# garden.net
KiCad netlist of a schematic drawn in EAGLE
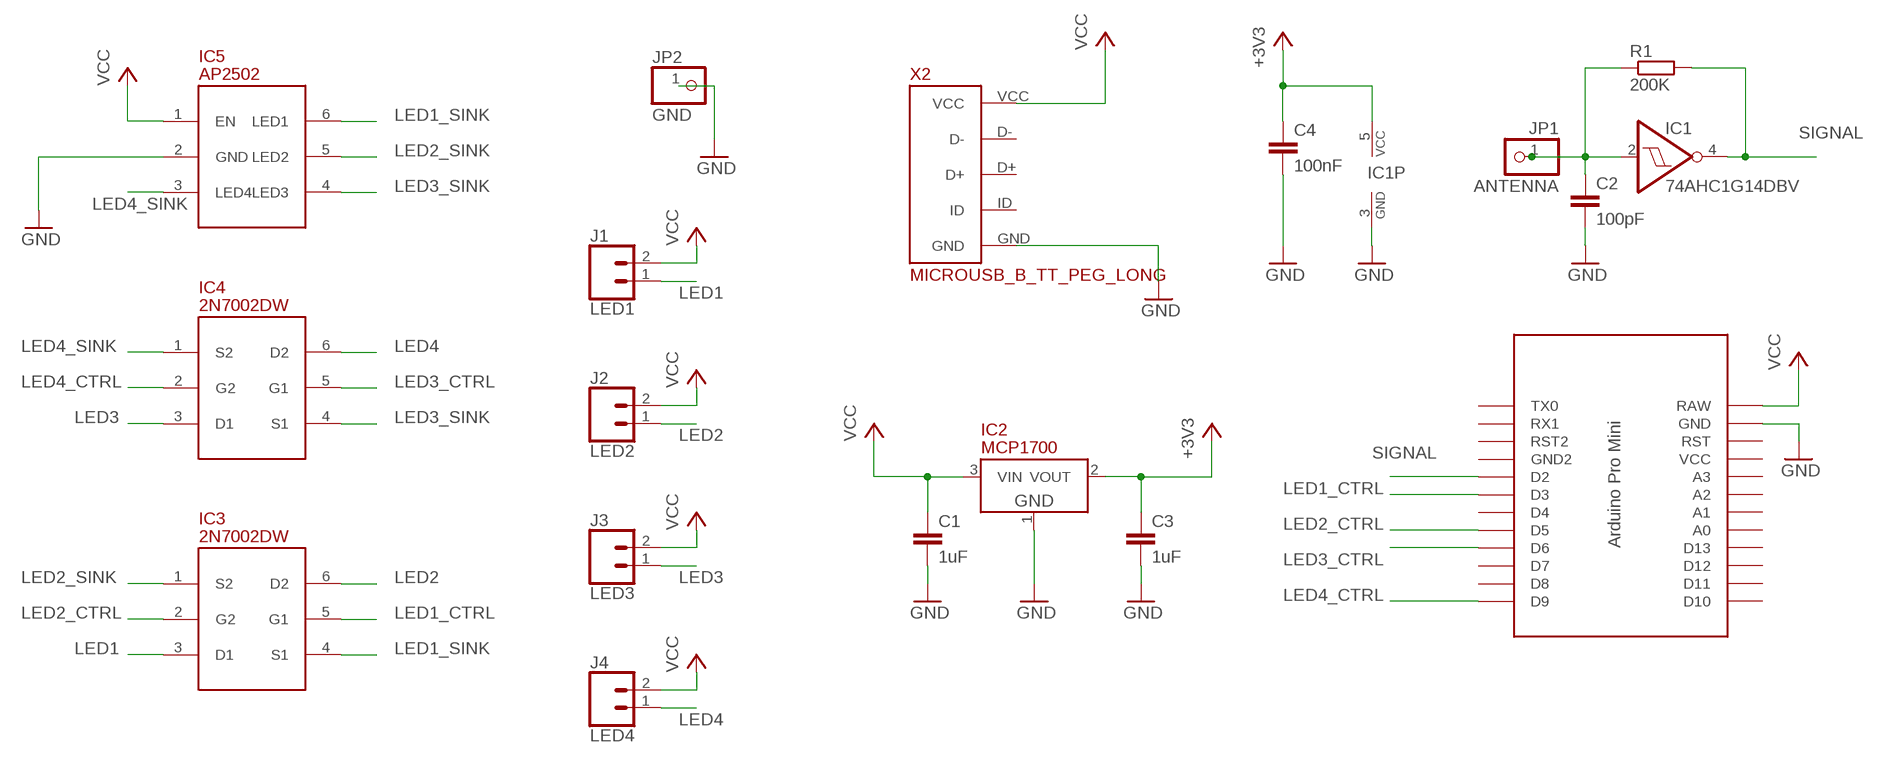
[diagram p0: schematic, sheet 1]

(export (version "E")
  (design (tool "Eeschema 10.0.6"))
  (components
    (comp (ref "C1")
      (value "1uF")
      (footprint "eagle-import:C0805")
      (libsource (lib "eagle-import") (part "C-EUC0805"))
    )
    (comp (ref "C2")
      (value "100pF")
      (footprint "eagle-import:C0805")
      (libsource (lib "eagle-import") (part "C-EUC0805"))
    )
    (comp (ref "C3")
      (value "1uF")
      (footprint "eagle-import:C0805")
      (libsource (lib "eagle-import") (part "C-EUC0805"))
    )
    (comp (ref "C4")
      (value "100nF")
      (footprint "eagle-import:C0805")
      (libsource (lib "eagle-import") (part "C-EUC0805"))
    )
    (comp (ref "IC1")
      (value "74AHC1G14DBV")
      (footprint "eagle-import:SOT23-5")
      (libsource (lib "eagle-import") (part "741G14DBVAHC"))
    )
    (comp (ref "IC2")
      (value "MCP1700")
      (footprint "eagle-import:SOT-23")
      (libsource (lib "eagle-import") (part "MCP1700"))
    )
    (comp (ref "IC3")
      (value "2N7002DW")
      (footprint "eagle-import:SOT363")
      (libsource (lib "eagle-import") (part "2N7002DW"))
    )
    (comp (ref "IC4")
      (value "2N7002DW")
      (footprint "eagle-import:SOT363")
      (libsource (lib "eagle-import") (part "2N7002DW"))
    )
    (comp (ref "IC5")
      (value "AP2502")
      (footprint "eagle-import:SOT-23-6")
      (libsource (lib "eagle-import") (part "AP2502"))
    )
    (comp (ref "J1")
      (value "LED1")
      (footprint "eagle-import:1X02")
      (libsource (lib "eagle-import") (part "CONN_02"))
    )
    (comp (ref "J2")
      (value "LED2")
      (footprint "eagle-import:1X02")
      (libsource (lib "eagle-import") (part "CONN_02"))
    )
    (comp (ref "J3")
      (value "LED3")
      (footprint "eagle-import:1X02")
      (libsource (lib "eagle-import") (part "CONN_02"))
    )
    (comp (ref "J4")
      (value "LED4")
      (footprint "eagle-import:1X02")
      (libsource (lib "eagle-import") (part "CONN_02"))
    )
    (comp (ref "JP1")
      (value "ANTENNA")
      (footprint "eagle-import:1X01")
      (libsource (lib "eagle-import") (part "PINHD-1X1"))
    )
    (comp (ref "JP2")
      (value "GND")
      (footprint "eagle-import:1X01")
      (libsource (lib "eagle-import") (part "PINHD-1X1"))
    )
    (comp (ref "R1")
      (value "200K")
      (footprint "eagle-import:R0805")
      (libsource (lib "eagle-import") (part "R-EU_R0805"))
    )
    (comp (ref "U$1")
      (value "PRO-MINI-TWO-SIDES-ONLY")
      (footprint "eagle-import:PRO-MINI-TWO-SIDES-ONLY")
      (libsource (lib "eagle-import") (part "PRO-MINI-TWO-SIDES-ONLY"))
    )
    (comp (ref "X2")
      (value "MICROUSB_B_TT_PEG_LONG")
      (footprint "eagle-import:MICROUSB_B_TT_PEG_LONG")
      (libsource (lib "eagle-import") (part "MICROUSB_B_TT_PEG_LONG"))
    )
  )
  (nets
    (net (code "1") (name "+3V3") (class "Default")
      (node (ref "C3") (pin "1") (pinfunction "1_1") (pintype "passive"))
      (node (ref "C4") (pin "1") (pinfunction "1_1") (pintype "passive"))
      (node (ref "IC1") (pin "5") (pinfunction "VCC_5") (pintype "power_in"))
      (node (ref "IC2") (pin "2") (pinfunction "VOUT_2") (pintype "output"))
    )
    (net (code "2") (name "/LED1") (class "Default")
      (node (ref "IC3") (pin "3") (pinfunction "D1_3") (pintype "input"))
      (node (ref "J1") (pin "1") (pinfunction "1_1") (pintype "passive"))
    )
    (net (code "3") (name "/LED1_CTRL") (class "Default")
      (node (ref "IC3") (pin "5") (pinfunction "G1_5") (pintype "input"))
      (node (ref "U$1") (pin "D3") (pinfunction "D3_D3") (pintype "bidirectional"))
    )
    (net (code "4") (name "/LED1_SINK") (class "Default")
      (node (ref "IC3") (pin "4") (pinfunction "S1_4") (pintype "output"))
      (node (ref "IC5") (pin "6") (pinfunction "LED1_6") (pintype "output"))
    )
    (net (code "5") (name "/LED2") (class "Default")
      (node (ref "IC3") (pin "6") (pinfunction "D2_6") (pintype "input"))
      (node (ref "J2") (pin "1") (pinfunction "1_1") (pintype "passive"))
    )
    (net (code "6") (name "/LED2_CTRL") (class "Default")
      (node (ref "IC3") (pin "2") (pinfunction "G2_2") (pintype "input"))
      (node (ref "U$1") (pin "D5") (pinfunction "D5_D5") (pintype "bidirectional"))
    )
    (net (code "7") (name "/LED2_SINK") (class "Default")
      (node (ref "IC3") (pin "1") (pinfunction "S2_1") (pintype "output"))
      (node (ref "IC5") (pin "5") (pinfunction "LED2_5") (pintype "output"))
    )
    (net (code "8") (name "/LED3") (class "Default")
      (node (ref "IC4") (pin "3") (pinfunction "D1_3") (pintype "input"))
      (node (ref "J3") (pin "1") (pinfunction "1_1") (pintype "passive"))
    )
    (net (code "9") (name "/LED3_CTRL") (class "Default")
      (node (ref "IC4") (pin "5") (pinfunction "G1_5") (pintype "input"))
      (node (ref "U$1") (pin "D6") (pinfunction "D6_D6") (pintype "bidirectional"))
    )
    (net (code "10") (name "/LED3_SINK") (class "Default")
      (node (ref "IC4") (pin "4") (pinfunction "S1_4") (pintype "output"))
      (node (ref "IC5") (pin "4") (pinfunction "LED3_4") (pintype "output"))
    )
    (net (code "11") (name "/LED4") (class "Default")
      (node (ref "IC4") (pin "6") (pinfunction "D2_6") (pintype "input"))
      (node (ref "J4") (pin "1") (pinfunction "1_1") (pintype "passive"))
    )
    (net (code "12") (name "/LED4_CTRL") (class "Default")
      (node (ref "IC4") (pin "2") (pinfunction "G2_2") (pintype "input"))
      (node (ref "U$1") (pin "D9") (pinfunction "D9_D9") (pintype "bidirectional"))
    )
    (net (code "13") (name "/LED4_SINK") (class "Default")
      (node (ref "IC4") (pin "1") (pinfunction "S2_1") (pintype "output"))
      (node (ref "IC5") (pin "3") (pinfunction "LED4_3") (pintype "output"))
    )
    (net (code "14") (name "/SIGNAL") (class "Default")
      (node (ref "IC1") (pin "4") (pinfunction "O_4") (pintype "output"))
      (node (ref "R1") (pin "2") (pinfunction "2_2") (pintype "passive"))
      (node (ref "U$1") (pin "D2") (pinfunction "D2_D2") (pintype "bidirectional"))
    )
    (net (code "15") (name "GND") (class "Default")
      (node (ref "C1") (pin "2") (pinfunction "2_2") (pintype "passive"))
      (node (ref "C2") (pin "2") (pinfunction "2_2") (pintype "passive"))
      (node (ref "C3") (pin "2") (pinfunction "2_2") (pintype "passive"))
      (node (ref "C4") (pin "2") (pinfunction "2_2") (pintype "passive"))
      (node (ref "IC1") (pin "3") (pinfunction "GND_3") (pintype "power_in"))
      (node (ref "IC2") (pin "1") (pinfunction "GND_1") (pintype "input"))
      (node (ref "IC5") (pin "2") (pinfunction "GND_2") (pintype "input"))
      (node (ref "JP2") (pin "1") (pinfunction "1_1") (pintype "passive"))
      (node (ref "U$1") (pin "GND") (pinfunction "GND_GND") (pintype "input"))
      (node (ref "X2") (pin "GND") (pinfunction "GND_GND") (pintype "power_in"))
    )
    (net (code "16") (name "Net-(IC1A-I)") (class "Default")
      (node (ref "C2") (pin "1") (pinfunction "1_1") (pintype "passive"))
      (node (ref "IC1") (pin "2") (pinfunction "I_2") (pintype "input"))
      (node (ref "JP1") (pin "1") (pinfunction "1_1") (pintype "passive"))
      (node (ref "R1") (pin "1") (pinfunction "1_1") (pintype "passive"))
    )
    (net (code "17") (name "VCC") (class "Default")
      (node (ref "C1") (pin "1") (pinfunction "1_1") (pintype "passive"))
      (node (ref "IC2") (pin "3") (pinfunction "VIN_3") (pintype "input"))
      (node (ref "IC5") (pin "1") (pinfunction "EN_1") (pintype "input"))
      (node (ref "J1") (pin "2") (pinfunction "2_2") (pintype "passive"))
      (node (ref "J2") (pin "2") (pinfunction "2_2") (pintype "passive"))
      (node (ref "J3") (pin "2") (pinfunction "2_2") (pintype "passive"))
      (node (ref "J4") (pin "2") (pinfunction "2_2") (pintype "passive"))
      (node (ref "U$1") (pin "RAW") (pinfunction "RAW_RAW") (pintype "power_in"))
      (node (ref "X2") (pin "VCC") (pinfunction "VCC_VCC") (pintype "power_in"))
    )
    (net (code "18") (name "unconnected-(U$1-GND2-PadGND1)") (class "Default")
      (node (ref "U$1") (pin "GND1") (pinfunction "GND2_GND1") (pintype "bidirectional"))
    )
    (net (code "19") (name "unconnected-(U$1-PadA0)") (class "Default")
      (node (ref "U$1") (pin "A0") (pinfunction "A0_A0") (pintype "bidirectional"))
    )
    (net (code "20") (name "unconnected-(U$1-PadA1)") (class "Default")
      (node (ref "U$1") (pin "A1") (pinfunction "A1_A1") (pintype "bidirectional"))
    )
    (net (code "21") (name "unconnected-(U$1-PadA2)") (class "Default")
      (node (ref "U$1") (pin "A2") (pinfunction "A2_A2") (pintype "bidirectional"))
    )
    (net (code "22") (name "unconnected-(U$1-PadA3)") (class "Default")
      (node (ref "U$1") (pin "A3") (pinfunction "A3_A3") (pintype "bidirectional"))
    )
    (net (code "23") (name "unconnected-(U$1-PadD4)") (class "Default")
      (node (ref "U$1") (pin "D4") (pinfunction "D4_D4") (pintype "bidirectional"))
    )
    (net (code "24") (name "unconnected-(U$1-PadD7)") (class "Default")
      (node (ref "U$1") (pin "D7") (pinfunction "D7_D7") (pintype "bidirectional"))
    )
    (net (code "25") (name "unconnected-(U$1-PadD8)") (class "Default")
      (node (ref "U$1") (pin "D8") (pinfunction "D8_D8") (pintype "bidirectional"))
    )
    (net (code "26") (name "unconnected-(U$1-PadD10)") (class "Default")
      (node (ref "U$1") (pin "D10") (pinfunction "D10_D10") (pintype "bidirectional"))
    )
    (net (code "27") (name "unconnected-(U$1-PadD11)") (class "Default")
      (node (ref "U$1") (pin "D11") (pinfunction "D11_D11") (pintype "bidirectional"))
    )
    (net (code "28") (name "unconnected-(U$1-PadD12)") (class "Default")
      (node (ref "U$1") (pin "D12") (pinfunction "D12_D12") (pintype "bidirectional"))
    )
    (net (code "29") (name "unconnected-(U$1-PadD13)") (class "Default")
      (node (ref "U$1") (pin "D13") (pinfunction "D13_D13") (pintype "bidirectional"))
    )
    (net (code "30") (name "unconnected-(U$1-PadRST)") (class "Default")
      (node (ref "U$1") (pin "RST") (pinfunction "RST_RST") (pintype "bidirectional"))
    )
    (net (code "31") (name "unconnected-(U$1-PadRX1)") (class "Default")
      (node (ref "U$1") (pin "RX1") (pinfunction "RX1_RX1") (pintype "bidirectional"))
    )
    (net (code "32") (name "unconnected-(U$1-PadTX0)") (class "Default")
      (node (ref "U$1") (pin "TX0") (pinfunction "TX0_TX0") (pintype "bidirectional"))
    )
    (net (code "33") (name "unconnected-(U$1-PadVCC)") (class "Default")
      (node (ref "U$1") (pin "VCC") (pinfunction "VCC_VCC") (pintype "bidirectional"))
    )
    (net (code "34") (name "unconnected-(U$1-RST2-PadRST1)") (class "Default")
      (node (ref "U$1") (pin "RST1") (pinfunction "RST2_RST1") (pintype "bidirectional"))
    )
    (net (code "35") (name "unconnected-(X2-PadD+)") (class "Default")
      (node (ref "X2") (pin "D+") (pinfunction "D+_D+") (pintype "bidirectional"))
    )
    (net (code "36") (name "unconnected-(X2-PadD-)") (class "Default")
      (node (ref "X2") (pin "D-") (pinfunction "D-_D-") (pintype "bidirectional"))
    )
    (net (code "37") (name "unconnected-(X2-PadID)") (class "Default")
      (node (ref "X2") (pin "ID") (pinfunction "ID_ID") (pintype "bidirectional"))
    )
  )
)
